# bpod_stepper_1_5_4.net
KiCad netlist of a schematic drawn in EAGLE
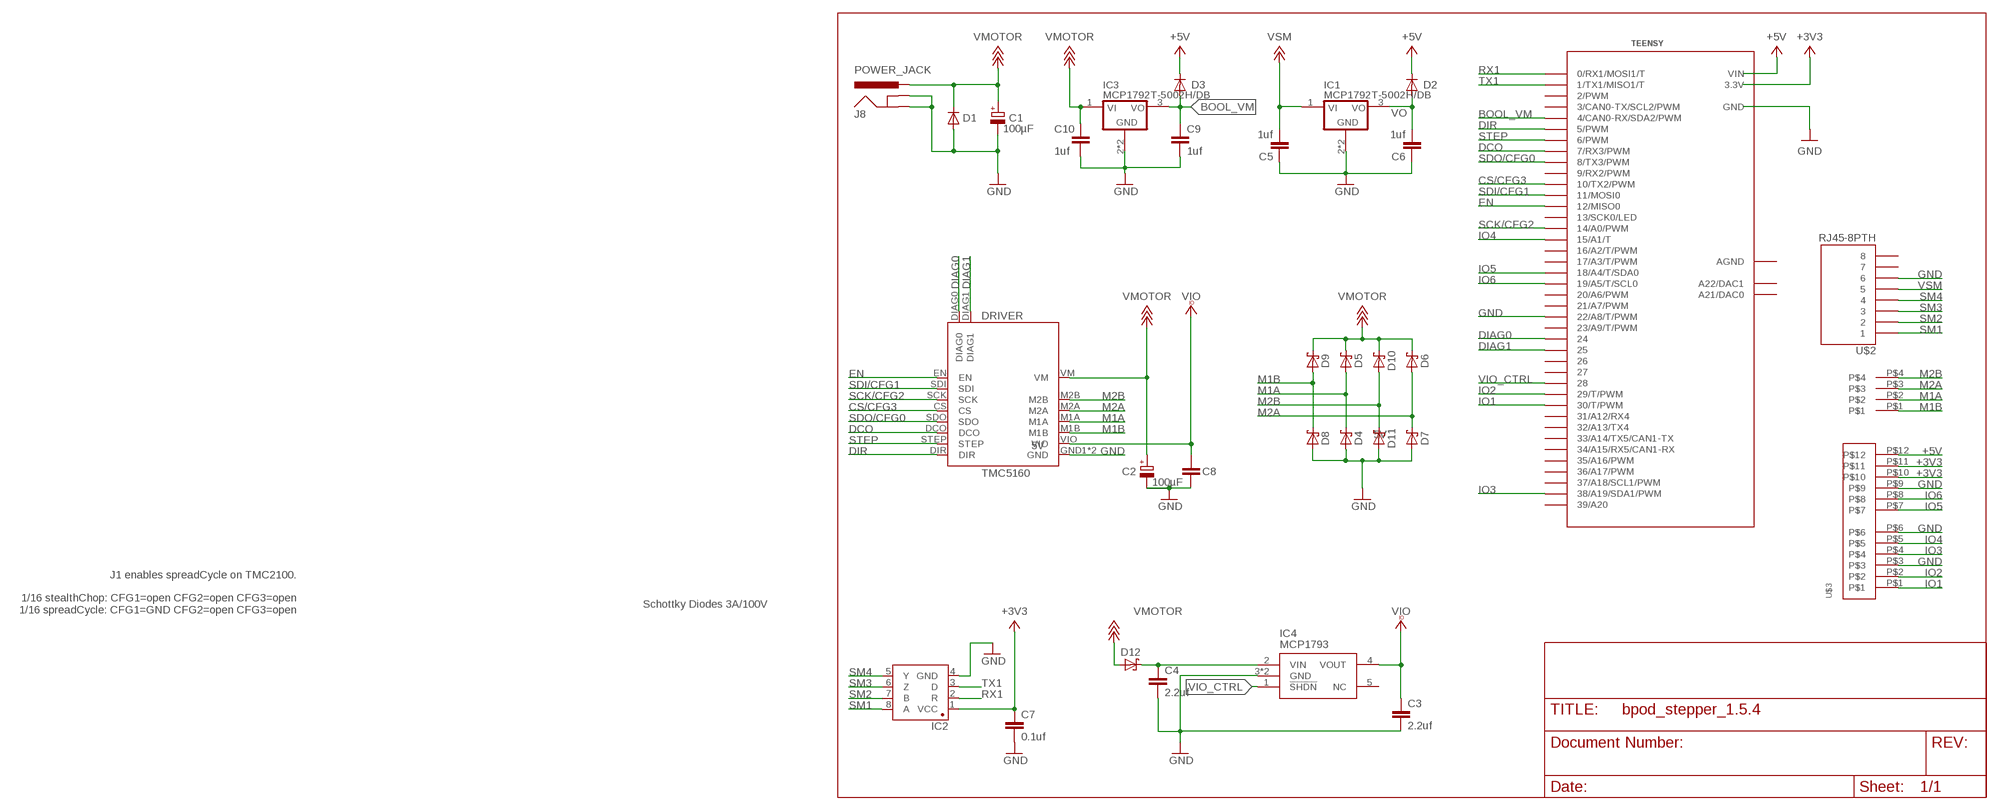
[diagram p0: schematic, sheet 1]

(export (version "E")
  (design (tool "Eeschema 10.0.6"))
  (components
    (comp (ref "C1")
      (value "100µF")
      (footprint "eagle-import:PANASONIC_G")
      (libsource (lib "eagle-import") (part "CPOL-EUG"))
    )
    (comp (ref "C2")
      (value "100µF")
      (footprint "eagle-import:PANASONIC_G")
      (libsource (lib "eagle-import") (part "CPOL-EUG"))
    )
    (comp (ref "C3")
      (value "2.2uf")
      (footprint "eagle-import:1206@1")
      (libsource (lib "eagle-import") (part "CAP1206"))
    )
    (comp (ref "C4")
      (value "2.2uf")
      (footprint "eagle-import:1206@1")
      (libsource (lib "eagle-import") (part "CAP1206"))
    )
    (comp (ref "C5")
      (value "1uf")
      (footprint "eagle-import:1206@1")
      (libsource (lib "eagle-import") (part "CAP1206"))
    )
    (comp (ref "C6")
      (value "1uf")
      (footprint "eagle-import:1206@1")
      (libsource (lib "eagle-import") (part "CAP1206"))
    )
    (comp (ref "C7")
      (value "0.1uf")
      (footprint "eagle-import:1206@1")
      (libsource (lib "eagle-import") (part "CAP1206"))
    )
    (comp (ref "C8")
      (value "100nf")
      (footprint "eagle-import:1206@1")
      (libsource (lib "eagle-import") (part "CAP1206"))
    )
    (comp (ref "C9")
      (value "1uf")
      (footprint "eagle-import:1206@1")
      (libsource (lib "eagle-import") (part "CAP1206"))
    )
    (comp (ref "C10")
      (value "1uf")
      (footprint "eagle-import:1206@1")
      (libsource (lib "eagle-import") (part "CAP1206"))
    )
    (comp (ref "D1")
      (value "DIODE-DO214AA")
      (footprint "eagle-import:DO214AA")
      (libsource (lib "eagle-import") (part "DIODE-DO214AA"))
    )
    (comp (ref "D2")
      (value "MBR0520LT")
      (footprint "eagle-import:SOD123")
      (libsource (lib "eagle-import") (part "MBR0520LT"))
    )
    (comp (ref "D3")
      (value "MBR0520LT")
      (footprint "eagle-import:SOD123")
      (libsource (lib "eagle-import") (part "MBR0520LT"))
    )
    (comp (ref "D4")
      (value "S310FA")
      (footprint "eagle-import:SOD123")
      (libsource (lib "eagle-import") (part "D_SCHOTTKY-SOD123"))
    )
    (comp (ref "D5")
      (value "S310FA")
      (footprint "eagle-import:SOD123")
      (libsource (lib "eagle-import") (part "D_SCHOTTKY-SOD123"))
    )
    (comp (ref "D6")
      (value "S310FA")
      (footprint "eagle-import:SOD123")
      (libsource (lib "eagle-import") (part "D_SCHOTTKY-SOD123"))
    )
    (comp (ref "D7")
      (value "S310FA")
      (footprint "eagle-import:SOD123")
      (libsource (lib "eagle-import") (part "D_SCHOTTKY-SOD123"))
    )
    (comp (ref "D8")
      (value "S310FA")
      (footprint "eagle-import:SOD123")
      (libsource (lib "eagle-import") (part "D_SCHOTTKY-SOD123"))
    )
    (comp (ref "D9")
      (value "S310FA")
      (footprint "eagle-import:SOD123")
      (libsource (lib "eagle-import") (part "D_SCHOTTKY-SOD123"))
    )
    (comp (ref "D10")
      (value "S310FA")
      (footprint "eagle-import:SOD123")
      (libsource (lib "eagle-import") (part "D_SCHOTTKY-SOD123"))
    )
    (comp (ref "D11")
      (value "S310FA")
      (footprint "eagle-import:SOD123")
      (libsource (lib "eagle-import") (part "D_SCHOTTKY-SOD123"))
    )
    (comp (ref "D12")
      (value "S310FA")
      (footprint "eagle-import:SOD123")
      (libsource (lib "eagle-import") (part "D_SCHOTTKY-SOD123"))
    )
    (comp (ref "DRIVER")
      (value "TMC5160")
      (footprint "eagle-import:TMC5160")
      (libsource (lib "eagle-import") (part "TMC5160"))
    )
    (comp (ref "IC1")
      (value "MCP1792T-5002H/DB")
      (footprint "eagle-import:SOT223")
      (libsource (lib "eagle-import") (part "MCP1792T-5002H/DB"))
    )
    (comp (ref "IC2")
      (value "SN65HVD31DR")
      (footprint "eagle-import:SO08")
      (libsource (lib "eagle-import") (part "SN65HVD31DR"))
    )
    (comp (ref "IC3")
      (value "MCP1792T-5002H/DB")
      (footprint "eagle-import:SOT223")
      (libsource (lib "eagle-import") (part "MCP1792T-5002H/DB"))
    )
    (comp (ref "IC4")
      (value "MCP1793")
      (footprint "eagle-import:SOT223-5")
      (libsource (lib "eagle-import") (part "MCP1793_SOT223-5"))
    )
    (comp (ref "J8")
      (value "POWER_JACK")
      (footprint "eagle-import:POWER_JACK_PTH")
      (libsource (lib "eagle-import") (part "POWER_JACK"))
    )
    (comp (ref "TEENSY")
      (value "TEENSY_3.6_DIL")
      (footprint "eagle-import:TEENSY_3.6_DIL")
      (libsource (lib "eagle-import") (part "TEENSY_3.6_DIL"))
    )
    (comp (ref "U$2")
      (value "RJ45-8PTH")
      (footprint "eagle-import:RJ45-8")
      (libsource (lib "eagle-import") (part "RJ45-8PTH"))
    )
    (comp (ref "U$3")
      (value "12POS_MOLEX_SOCKET")
      (footprint "eagle-import:12POS_MOLEX_SOCKET")
      (libsource (lib "eagle-import") (part "12POS_MOLEX_SOCKET"))
    )
    (comp (ref "U$4")
      (value "MOLEX395221004")
      (footprint "eagle-import:MOLEX395221004")
      (libsource (lib "eagle-import") (part "MOLEX395221004"))
    )
  )
  (nets
    (net (code "1") (name "+3V3") (class "Default")
      (node (ref "C7") (pin "1") (pinfunction "1_1") (pintype "passive"))
      (node (ref "IC2") (pin "1") (pinfunction "VCC_1") (pintype "bidirectional"))
      (node (ref "TEENSY") (pin "3.3V") (pinfunction "3.3V_3.3V") (pintype "power_in"))
      (node (ref "TEENSY") (pin "3.3V3") (pinfunction "3.3V_3.3V3") (pintype "power_in"))
      (node (ref "U$3") (pin "P$10") (pinfunction "P$10_P$10") (pintype "bidirectional"))
      (node (ref "U$3") (pin "P$11") (pinfunction "P$11_P$11") (pintype "bidirectional"))
    )
    (net (code "2") (name "+5V") (class "Default")
      (node (ref "D2") (pin "C") (pinfunction "C_C") (pintype "passive"))
      (node (ref "D3") (pin "C") (pinfunction "C_C") (pintype "passive"))
      (node (ref "TEENSY") (pin "VIN") (pinfunction "VIN_VIN") (pintype "power_in"))
      (node (ref "U$3") (pin "P$12") (pinfunction "P$12_P$12") (pintype "bidirectional"))
    )
    (net (code "3") (name "+12V") (class "Default")
      (node (ref "C5") (pin "2") (pinfunction "2_2") (pintype "passive"))
      (node (ref "IC1") (pin "1") (pinfunction "VI_1") (pintype "power_in"))
      (node (ref "U$2") (pin "5") (pinfunction "5_5") (pintype "bidirectional"))
    )
    (net (code "4") (name "+18V") (class "Default")
      (node (ref "C1") (pin "+") (pinfunction "+_+") (pintype "passive"))
      (node (ref "C10") (pin "1") (pinfunction "1_1") (pintype "passive"))
      (node (ref "C2") (pin "+") (pinfunction "+_+") (pintype "passive"))
      (node (ref "D1") (pin "C") (pinfunction "C_C") (pintype "passive"))
      (node (ref "D10") (pin "C") (pinfunction "C_C") (pintype "passive"))
      (node (ref "D12") (pin "A") (pinfunction "A_A") (pintype "passive"))
      (node (ref "D5") (pin "C") (pinfunction "C_C") (pintype "passive"))
      (node (ref "D6") (pin "C") (pinfunction "C_C") (pintype "passive"))
      (node (ref "D9") (pin "C") (pinfunction "C_C") (pintype "passive"))
      (node (ref "DRIVER") (pin "VM") (pinfunction "VM_VM") (pintype "power_in"))
      (node (ref "IC3") (pin "1") (pinfunction "VI_1") (pintype "power_in"))
      (node (ref "J8") (pin "PWR") (pinfunction "PWR_PWR") (pintype "bidirectional"))
    )
    (net (code "5") (name "/AGND") (class "Default")
      (node (ref "TEENSY") (pin "AGND") (pinfunction "AGND_AGND") (pintype "power_in"))
    )
    (net (code "6") (name "/CS{slash}CFG3") (class "Default")
      (node (ref "DRIVER") (pin "CS") (pinfunction "CS_CS") (pintype "passive"))
      (node (ref "TEENSY") (pin "10") (pinfunction "10/TX2/PWM_10") (pintype "bidirectional"))
    )
    (net (code "7") (name "/DCO") (class "Default")
      (node (ref "DRIVER") (pin "DCO") (pinfunction "DCO_DCO") (pintype "passive"))
      (node (ref "TEENSY") (pin "7") (pinfunction "7/RX3/PWM_7") (pintype "bidirectional"))
    )
    (net (code "8") (name "/DIAG0") (class "Default")
      (node (ref "DRIVER") (pin "DIAG0") (pinfunction "DIAG0_DIAG0") (pintype "passive"))
      (node (ref "TEENSY") (pin "24") (pinfunction "24_24") (pintype "bidirectional"))
    )
    (net (code "9") (name "/DIAG1") (class "Default")
      (node (ref "DRIVER") (pin "DIAG1") (pinfunction "DIAG1_DIAG1") (pintype "passive"))
      (node (ref "TEENSY") (pin "25") (pinfunction "25_25") (pintype "bidirectional"))
    )
    (net (code "10") (name "/DIR") (class "Default")
      (node (ref "DRIVER") (pin "DIR") (pinfunction "DIR_DIR") (pintype "input"))
      (node (ref "TEENSY") (pin "5") (pinfunction "5/PWM_5") (pintype "bidirectional"))
    )
    (net (code "11") (name "/EN") (class "Default")
      (node (ref "DRIVER") (pin "EN") (pinfunction "EN_EN") (pintype "passive"))
      (node (ref "TEENSY") (pin "12") (pinfunction "12/MISO0_12") (pintype "bidirectional"))
    )
    (net (code "12") (name "/IO1") (class "Default")
      (node (ref "TEENSY") (pin "30") (pinfunction "30/T/PWM_30") (pintype "bidirectional"))
      (node (ref "U$3") (pin "P$1") (pinfunction "P$1_P$1") (pintype "bidirectional"))
    )
    (net (code "13") (name "/IO2") (class "Default")
      (node (ref "TEENSY") (pin "29") (pinfunction "29/T/PWM_29") (pintype "bidirectional"))
      (node (ref "U$3") (pin "P$2") (pinfunction "P$2_P$2") (pintype "bidirectional"))
    )
    (net (code "14") (name "/IO3") (class "Default")
      (node (ref "TEENSY") (pin "38/A19") (pinfunction "38/A19/SDA1/PWM_38/A19") (pintype "bidirectional"))
      (node (ref "U$3") (pin "P$4") (pinfunction "P$4_P$4") (pintype "bidirectional"))
    )
    (net (code "15") (name "/IO4") (class "Default")
      (node (ref "TEENSY") (pin "15/A1") (pinfunction "15/A1/T_15/A1") (pintype "bidirectional"))
      (node (ref "U$3") (pin "P$5") (pinfunction "P$5_P$5") (pintype "bidirectional"))
    )
    (net (code "16") (name "/IO5") (class "Default")
      (node (ref "TEENSY") (pin "18/A4") (pinfunction "18/A4/T/SDA0_18/A4") (pintype "bidirectional"))
      (node (ref "U$3") (pin "P$7") (pinfunction "P$7_P$7") (pintype "bidirectional"))
    )
    (net (code "17") (name "/IO6") (class "Default")
      (node (ref "TEENSY") (pin "19/A5") (pinfunction "19/A5/T/SCL0_19/A5") (pintype "bidirectional"))
      (node (ref "U$3") (pin "P$8") (pinfunction "P$8_P$8") (pintype "bidirectional"))
    )
    (net (code "18") (name "/M1A") (class "Default")
      (node (ref "D4") (pin "C") (pinfunction "C_C") (pintype "passive"))
      (node (ref "D5") (pin "A") (pinfunction "A_A") (pintype "passive"))
      (node (ref "DRIVER") (pin "M1A") (pinfunction "M1A_M1A") (pintype "output"))
      (node (ref "U$4") (pin "P$2") (pinfunction "P$2_P$2") (pintype "bidirectional"))
    )
    (net (code "19") (name "/M1B") (class "Default")
      (node (ref "D8") (pin "C") (pinfunction "C_C") (pintype "passive"))
      (node (ref "D9") (pin "A") (pinfunction "A_A") (pintype "passive"))
      (node (ref "DRIVER") (pin "M1B") (pinfunction "M1B_M1B") (pintype "output"))
      (node (ref "U$4") (pin "P$1") (pinfunction "P$1_P$1") (pintype "bidirectional"))
    )
    (net (code "20") (name "/M2A") (class "Default")
      (node (ref "D6") (pin "A") (pinfunction "A_A") (pintype "passive"))
      (node (ref "D7") (pin "C") (pinfunction "C_C") (pintype "passive"))
      (node (ref "DRIVER") (pin "M2A") (pinfunction "M2A_M2A") (pintype "output"))
      (node (ref "U$4") (pin "P$3") (pinfunction "P$3_P$3") (pintype "bidirectional"))
    )
    (net (code "21") (name "/M2B") (class "Default")
      (node (ref "D10") (pin "A") (pinfunction "A_A") (pintype "passive"))
      (node (ref "D11") (pin "C") (pinfunction "C_C") (pintype "passive"))
      (node (ref "DRIVER") (pin "M2B") (pinfunction "M2B_M2B") (pintype "output"))
      (node (ref "U$4") (pin "P$4") (pinfunction "P$4_P$4") (pintype "bidirectional"))
    )
    (net (code "22") (name "/RX1") (class "Default")
      (node (ref "IC2") (pin "2") (pinfunction "R_2") (pintype "bidirectional"))
      (node (ref "TEENSY") (pin "0") (pinfunction "0/RX1/MOSI1/T_0") (pintype "bidirectional"))
    )
    (net (code "23") (name "/SCK{slash}CFG2") (class "Default")
      (node (ref "DRIVER") (pin "SCK") (pinfunction "SCK_SCK") (pintype "passive"))
      (node (ref "TEENSY") (pin "14/A0") (pinfunction "14/A0/PWM_14/A0") (pintype "bidirectional"))
    )
    (net (code "24") (name "/SDI{slash}CFG1") (class "Default")
      (node (ref "DRIVER") (pin "SDI") (pinfunction "SDI_SDI") (pintype "passive"))
      (node (ref "TEENSY") (pin "11") (pinfunction "11/MOSI0_11") (pintype "bidirectional"))
    )
    (net (code "25") (name "/SDO{slash}CFG0") (class "Default")
      (node (ref "DRIVER") (pin "SDO") (pinfunction "SDO_SDO") (pintype "passive"))
      (node (ref "TEENSY") (pin "8") (pinfunction "8/TX3/PWM_8") (pintype "bidirectional"))
    )
    (net (code "26") (name "/SM1") (class "Default")
      (node (ref "IC2") (pin "8") (pinfunction "A_8") (pintype "bidirectional"))
      (node (ref "U$2") (pin "1") (pinfunction "1_1") (pintype "bidirectional"))
    )
    (net (code "27") (name "/SM2") (class "Default")
      (node (ref "IC2") (pin "7") (pinfunction "B_7") (pintype "bidirectional"))
      (node (ref "U$2") (pin "2") (pinfunction "2_2") (pintype "bidirectional"))
    )
    (net (code "28") (name "/SM3") (class "Default")
      (node (ref "IC2") (pin "6") (pinfunction "Z_6") (pintype "bidirectional"))
      (node (ref "U$2") (pin "3") (pinfunction "3_3") (pintype "bidirectional"))
    )
    (net (code "29") (name "/SM4") (class "Default")
      (node (ref "IC2") (pin "5") (pinfunction "Y_5") (pintype "bidirectional"))
      (node (ref "U$2") (pin "4") (pinfunction "4_4") (pintype "bidirectional"))
    )
    (net (code "30") (name "/STEP") (class "Default")
      (node (ref "DRIVER") (pin "STEP") (pinfunction "STEP_STEP") (pintype "input"))
      (node (ref "TEENSY") (pin "6") (pinfunction "6/PWM_6") (pintype "bidirectional"))
    )
    (net (code "31") (name "/TX1") (class "Default")
      (node (ref "IC2") (pin "3") (pinfunction "D_3") (pintype "bidirectional"))
      (node (ref "TEENSY") (pin "1") (pinfunction "1/TX1/MISO1/T_1") (pintype "bidirectional"))
    )
    (net (code "32") (name "/VO") (class "Default")
      (node (ref "C6") (pin "2") (pinfunction "2_2") (pintype "passive"))
      (node (ref "D2") (pin "A") (pinfunction "A_A") (pintype "passive"))
      (node (ref "IC1") (pin "3") (pinfunction "VO_3") (pintype "passive"))
    )
    (net (code "33") (name "BOOL_VM") (class "Default")
      (node (ref "C9") (pin "1") (pinfunction "1_1") (pintype "passive"))
      (node (ref "D3") (pin "A") (pinfunction "A_A") (pintype "passive"))
      (node (ref "IC3") (pin "3") (pinfunction "VO_3") (pintype "passive"))
      (node (ref "TEENSY") (pin "4") (pinfunction "4/CAN0-RX/SDA2/PWM_4") (pintype "bidirectional"))
    )
    (net (code "34") (name "GND") (class "Default")
      (node (ref "C1") (pin "-") (pinfunction "-_-") (pintype "passive"))
      (node (ref "C10") (pin "2") (pinfunction "2_2") (pintype "passive"))
      (node (ref "C2") (pin "-") (pinfunction "-_-") (pintype "passive"))
      (node (ref "C3") (pin "2") (pinfunction "2_2") (pintype "passive"))
      (node (ref "C4") (pin "2") (pinfunction "2_2") (pintype "passive"))
      (node (ref "C5") (pin "1") (pinfunction "1_1") (pintype "passive"))
      (node (ref "C6") (pin "1") (pinfunction "1_1") (pintype "passive"))
      (node (ref "C7") (pin "2") (pinfunction "2_2") (pintype "passive"))
      (node (ref "C8") (pin "2") (pinfunction "2_2") (pintype "passive"))
      (node (ref "C9") (pin "2") (pinfunction "2_2") (pintype "passive"))
      (node (ref "D1") (pin "A") (pinfunction "A_A") (pintype "passive"))
      (node (ref "D11") (pin "A") (pinfunction "A_A") (pintype "passive"))
      (node (ref "D4") (pin "A") (pinfunction "A_A") (pintype "passive"))
      (node (ref "D7") (pin "A") (pinfunction "A_A") (pintype "passive"))
      (node (ref "D8") (pin "A") (pinfunction "A_A") (pintype "passive"))
      (node (ref "DRIVER") (pin "GND1") (pinfunction "GND_GND1") (pintype "power_in"))
      (node (ref "DRIVER") (pin "GND2") (pinfunction "GND_GND2") (pintype "power_in"))
      (node (ref "IC1") (pin "2") (pinfunction "GND_2") (pintype "power_in"))
      (node (ref "IC1") (pin "4") (pinfunction "GND_4") (pintype "power_in"))
      (node (ref "IC2") (pin "4") (pinfunction "GND_4") (pintype "bidirectional"))
      (node (ref "IC3") (pin "2") (pinfunction "GND_2") (pintype "power_in"))
      (node (ref "IC3") (pin "4") (pinfunction "GND_4") (pintype "power_in"))
      (node (ref "IC4") (pin "3") (pinfunction "GND_3") (pintype "bidirectional"))
      (node (ref "IC4") (pin "6") (pinfunction "GND_6") (pintype "bidirectional"))
      (node (ref "J8") (pin "GND") (pinfunction "GND_GND") (pintype "bidirectional"))
      (node (ref "J8") (pin "GNDBREAK") (pinfunction "GNDBREAK_GNDBREAK") (pintype "bidirectional"))
      (node (ref "TEENSY") (pin "22/A8") (pinfunction "22/A8/T/PWM_22/A8") (pintype "bidirectional"))
      (node (ref "TEENSY") (pin "GND") (pinfunction "GND_GND") (pintype "power_in"))
      (node (ref "TEENSY") (pin "GND1") (pinfunction "GND_GND1") (pintype "power_in"))
      (node (ref "U$2") (pin "6") (pinfunction "6_6") (pintype "bidirectional"))
      (node (ref "U$3") (pin "P$3") (pinfunction "P$3_P$3") (pintype "bidirectional"))
      (node (ref "U$3") (pin "P$6") (pinfunction "P$6_P$6") (pintype "bidirectional"))
      (node (ref "U$3") (pin "P$9") (pinfunction "P$9_P$9") (pintype "bidirectional"))
    )
    (net (code "35") (name "Net-(IC4-VIN)") (class "Default")
      (node (ref "C4") (pin "1") (pinfunction "1_1") (pintype "passive"))
      (node (ref "D12") (pin "C") (pinfunction "C_C") (pintype "passive"))
      (node (ref "IC4") (pin "2") (pinfunction "VIN_2") (pintype "bidirectional"))
    )
    (net (code "36") (name "VCCIO") (class "Default")
      (node (ref "C3") (pin "1") (pinfunction "1_1") (pintype "passive"))
      (node (ref "C8") (pin "1") (pinfunction "1_1") (pintype "passive"))
      (node (ref "DRIVER") (pin "VIO") (pinfunction "VIO_VIO") (pintype "power_in"))
      (node (ref "IC4") (pin "4") (pinfunction "VOUT_4") (pintype "bidirectional"))
    )
    (net (code "37") (name "VIO_CTRL") (class "Default")
      (node (ref "IC4") (pin "1") (pinfunction "~{SHDN}_1") (pintype "bidirectional"))
      (node (ref "TEENSY") (pin "28") (pinfunction "28_28") (pintype "bidirectional"))
    )
    (net (code "38") (name "unconnected-(IC4-NC-Pad5)") (class "Default")
      (node (ref "IC4") (pin "5") (pinfunction "NC_5") (pintype "bidirectional"))
    )
    (net (code "39") (name "unconnected-(TEENSY-2{slash}PWM-Pad2)") (class "Default")
      (node (ref "TEENSY") (pin "2") (pinfunction "2/PWM_2") (pintype "bidirectional"))
    )
    (net (code "40") (name "unconnected-(TEENSY-3{slash}CAN0-TX{slash}SCL2{slash}PWM-Pad3)") (class "Default")
      (node (ref "TEENSY") (pin "3") (pinfunction "3/CAN0-TX/SCL2/PWM_3") (pintype "bidirectional"))
    )
    (net (code "41") (name "unconnected-(TEENSY-9{slash}RX2{slash}PWM-Pad9)") (class "Default")
      (node (ref "TEENSY") (pin "9") (pinfunction "9/RX2/PWM_9") (pintype "bidirectional"))
    )
    (net (code "42") (name "unconnected-(TEENSY-13{slash}SCK0{slash}LED-Pad13)") (class "Default")
      (node (ref "TEENSY") (pin "13") (pinfunction "13/SCK0/LED_13") (pintype "bidirectional"))
    )
    (net (code "43") (name "unconnected-(TEENSY-16{slash}A2{slash}T{slash}PWM-Pad16{slash}A2)") (class "Default")
      (node (ref "TEENSY") (pin "16/A2") (pinfunction "16/A2/T/PWM_16/A2") (pintype "bidirectional"))
    )
    (net (code "44") (name "unconnected-(TEENSY-17{slash}A3{slash}T{slash}PWM-Pad17{slash}A3)") (class "Default")
      (node (ref "TEENSY") (pin "17/A3") (pinfunction "17/A3/T/PWM_17/A3") (pintype "bidirectional"))
    )
    (net (code "45") (name "unconnected-(TEENSY-20{slash}A6{slash}PWM-Pad20{slash}A6)") (class "Default")
      (node (ref "TEENSY") (pin "20/A6") (pinfunction "20/A6/PWM_20/A6") (pintype "bidirectional"))
    )
    (net (code "46") (name "unconnected-(TEENSY-21{slash}A7{slash}PWM-Pad21{slash}A7)") (class "Default")
      (node (ref "TEENSY") (pin "21/A7") (pinfunction "21/A7/PWM_21/A7") (pintype "bidirectional"))
    )
    (net (code "47") (name "unconnected-(TEENSY-23{slash}A9{slash}T{slash}PWM-Pad23{slash}A9)") (class "Default")
      (node (ref "TEENSY") (pin "23/A9") (pinfunction "23/A9/T/PWM_23/A9") (pintype "bidirectional"))
    )
    (net (code "48") (name "unconnected-(TEENSY-31{slash}A12{slash}RX4-Pad31{slash}A12)") (class "Default")
      (node (ref "TEENSY") (pin "31/A12") (pinfunction "31/A12/RX4_31/A12") (pintype "bidirectional"))
    )
    (net (code "49") (name "unconnected-(TEENSY-32{slash}A13{slash}TX4-Pad32{slash}A13)") (class "Default")
      (node (ref "TEENSY") (pin "32/A13") (pinfunction "32/A13/TX4_32/A13") (pintype "bidirectional"))
    )
    (net (code "50") (name "unconnected-(TEENSY-33{slash}A14{slash}TX5{slash}CAN1-TX-Pad33{slash}A14)") (class "Default")
      (node (ref "TEENSY") (pin "33/A14") (pinfunction "33/A14/TX5/CAN1-TX_33/A14") (pintype "bidirectional"))
    )
    (net (code "51") (name "unconnected-(TEENSY-34{slash}A15{slash}RX5{slash}CAN1-RX-Pad34{slash}A15)") (class "Default")
      (node (ref "TEENSY") (pin "34/A15") (pinfunction "34/A15/RX5/CAN1-RX_34/A15") (pintype "bidirectional"))
    )
    (net (code "52") (name "unconnected-(TEENSY-35{slash}A16{slash}PWM-Pad35{slash}A16)") (class "Default")
      (node (ref "TEENSY") (pin "35/A16") (pinfunction "35/A16/PWM_35/A16") (pintype "bidirectional"))
    )
    (net (code "53") (name "unconnected-(TEENSY-36{slash}A17{slash}PWM-Pad36{slash}A17)") (class "Default")
      (node (ref "TEENSY") (pin "36/A17") (pinfunction "36/A17/PWM_36/A17") (pintype "bidirectional"))
    )
    (net (code "54") (name "unconnected-(TEENSY-37{slash}A18{slash}SCL1{slash}PWM-Pad37{slash}A18)") (class "Default")
      (node (ref "TEENSY") (pin "37/A18") (pinfunction "37/A18/SCL1/PWM_37/A18") (pintype "bidirectional"))
    )
    (net (code "55") (name "unconnected-(TEENSY-A21{slash}DAC0-PadA21)") (class "Default")
      (node (ref "TEENSY") (pin "A21") (pinfunction "A21/DAC0_A21") (pintype "bidirectional"))
    )
    (net (code "56") (name "unconnected-(TEENSY-A22{slash}DAC1-PadA22)") (class "Default")
      (node (ref "TEENSY") (pin "A22") (pinfunction "A22/DAC1_A22") (pintype "bidirectional"))
    )
    (net (code "57") (name "unconnected-(TEENSY-Pad26)") (class "Default")
      (node (ref "TEENSY") (pin "26") (pinfunction "26_26") (pintype "bidirectional"))
    )
    (net (code "58") (name "unconnected-(TEENSY-Pad27)") (class "Default")
      (node (ref "TEENSY") (pin "27") (pinfunction "27_27") (pintype "bidirectional"))
    )
    (net (code "59") (name "unconnected-(TEENSY-Pad39{slash}A20)") (class "Default")
      (node (ref "TEENSY") (pin "39/A20") (pinfunction "39/A20_39/A20") (pintype "bidirectional"))
    )
    (net (code "60") (name "unconnected-(U$2-Pad7)") (class "Default")
      (node (ref "U$2") (pin "7") (pinfunction "7_7") (pintype "bidirectional"))
    )
    (net (code "61") (name "unconnected-(U$2-Pad8)") (class "Default")
      (node (ref "U$2") (pin "8") (pinfunction "8_8") (pintype "bidirectional"))
    )
  )
)
